# penguat_daya_kelas_a.net
KiCad netlist of a schematic drawn in EAGLE
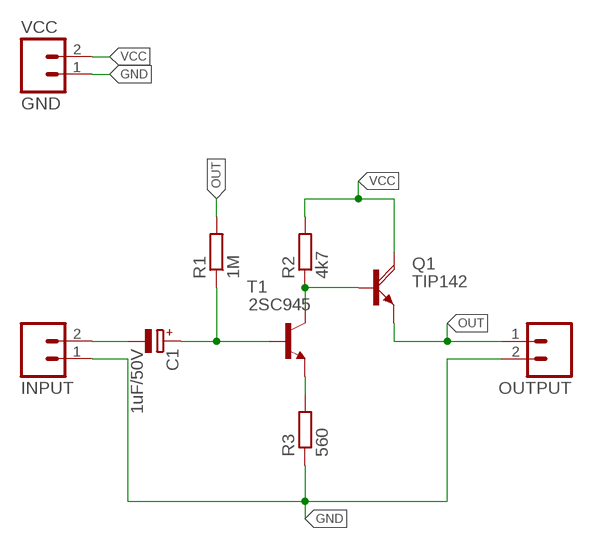
[diagram p0: schematic, sheet 1]

(export (version "E")
  (design (tool "Eeschema 10.0.6"))
  (components
    (comp (ref "C1")
      (value "1uF/50V")
      (footprint "eagle-import:E3,5-8")
      (libsource (lib "eagle-import") (part "CPOL-EUE3.5-8"))
    )
    (comp (ref "INPUT")
      (value "INPUT")
      (footprint "eagle-import:02P")
      (libsource (lib "eagle-import") (part "M02"))
    )
    (comp (ref "OUTPUT")
      (value "OUTPUT")
      (footprint "eagle-import:02P")
      (libsource (lib "eagle-import") (part "M02"))
    )
    (comp (ref "Q1")
      (value "TIP142")
      (footprint "eagle-import:SOT93")
      (libsource (lib "eagle-import") (part "TIP142"))
    )
    (comp (ref "R1")
      (value "1M")
      (footprint "eagle-import:0204_7")
      (libsource (lib "eagle-import") (part "R-EU_0204/7"))
    )
    (comp (ref "R2")
      (value "4k7")
      (footprint "eagle-import:0204_7")
      (libsource (lib "eagle-import") (part "R-EU_0204/7"))
    )
    (comp (ref "R3")
      (value "560")
      (footprint "eagle-import:0204_7")
      (libsource (lib "eagle-import") (part "R-EU_0204/7"))
    )
    (comp (ref "T1")
      (value "2SC945")
      (footprint "eagle-import:TO92-ECB")
      (libsource (lib "eagle-import") (part "2SC945"))
    )
    (comp (ref "VCC")
      (value "GND")
      (footprint "eagle-import:02P")
      (libsource (lib "eagle-import") (part "M02"))
    )
  )
  (nets
    (net (code "1") (name "GND") (class "Default")
      (node (ref "INPUT") (pin "1") (pinfunction "1_1") (pintype "passive"))
      (node (ref "OUTPUT") (pin "2") (pinfunction "2_2") (pintype "passive"))
      (node (ref "R3") (pin "1") (pinfunction "1_1") (pintype "passive"))
      (node (ref "VCC") (pin "1") (pinfunction "1_1") (pintype "passive"))
    )
    (net (code "2") (name "Net-(C1-Pad+)") (class "Default")
      (node (ref "C1") (pin "+") (pinfunction "+_+") (pintype "passive"))
      (node (ref "R1") (pin "1") (pinfunction "1_1") (pintype "passive"))
      (node (ref "T1") (pin "B") (pinfunction "B_B") (pintype "passive"))
    )
    (net (code "3") (name "Net-(C1-Pad-)") (class "Default")
      (node (ref "C1") (pin "-") (pinfunction "-_-") (pintype "passive"))
      (node (ref "INPUT") (pin "2") (pinfunction "2_2") (pintype "passive"))
    )
    (net (code "4") (name "Net-(Q1-PadB)") (class "Default")
      (node (ref "Q1") (pin "B") (pinfunction "B_B") (pintype "passive"))
      (node (ref "R2") (pin "1") (pinfunction "1_1") (pintype "passive"))
      (node (ref "T1") (pin "C") (pinfunction "C_C") (pintype "passive"))
    )
    (net (code "5") (name "Net-(R3-Pad2)") (class "Default")
      (node (ref "R3") (pin "2") (pinfunction "2_2") (pintype "passive"))
      (node (ref "T1") (pin "E") (pinfunction "E_E") (pintype "passive"))
    )
    (net (code "6") (name "OUT") (class "Default")
      (node (ref "OUTPUT") (pin "1") (pinfunction "1_1") (pintype "passive"))
      (node (ref "Q1") (pin "E") (pinfunction "E_E") (pintype "passive"))
      (node (ref "R1") (pin "2") (pinfunction "2_2") (pintype "passive"))
    )
    (net (code "7") (name "VCC") (class "Default")
      (node (ref "Q1") (pin "C") (pinfunction "C_C") (pintype "passive"))
      (node (ref "R2") (pin "2") (pinfunction "2_2") (pintype "passive"))
      (node (ref "VCC") (pin "2") (pinfunction "2_2") (pintype "passive"))
    )
  )
)
